# CPU.net
KiCad netlist of a schematic drawn in Altium Designer
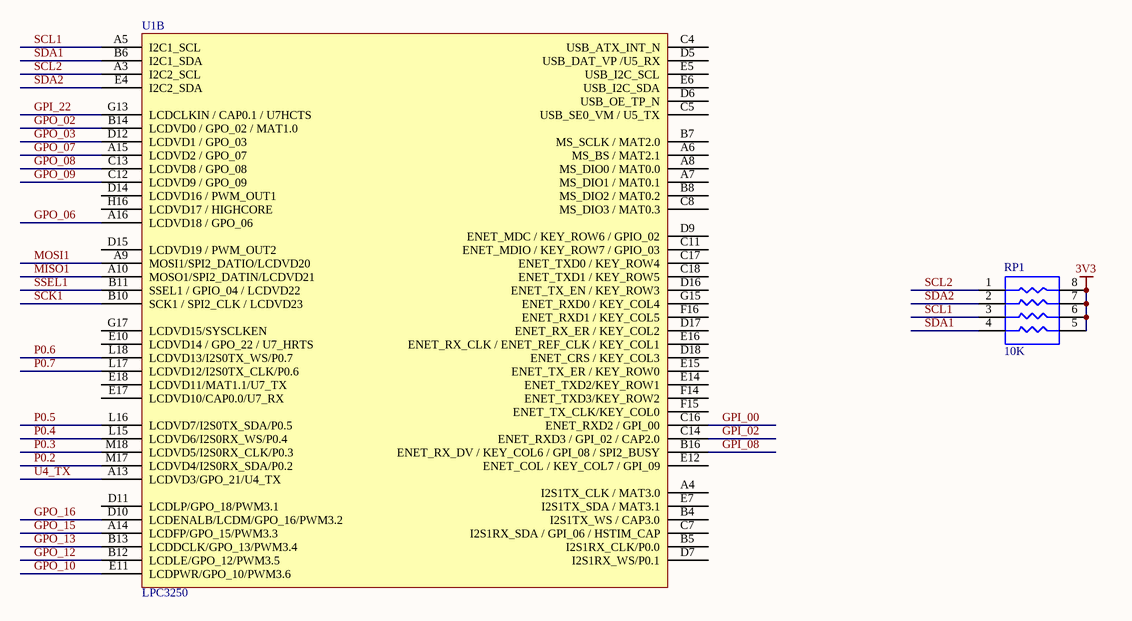
[diagram p0: CPU.SchDoc]

(export (version "E")
  (design (tool "Eeschema 10.0.6"))
  (components
    (comp (ref "RP1") (value "10K") (footprint "PZ-4-0.8B") (libsource (lib "MyProject1") (part "RP")))
    (comp (ref "U1") (value "LPC3250") (footprint "TFBGA296") (libsource (lib "MyProject1") (part "LPC3250")))
  )
  (nets
    (net (code "1") (name "/GPI_00") (class "Default")
      (node (ref "U1") (pin "C16") (pinfunction "ENET_RXD2_/_GPI_00_C16") (pintype "passive"))
    )
    (net (code "2") (name "/GPI_02") (class "Default")
      (node (ref "U1") (pin "C14") (pinfunction "ENET_RXD3_/_GPI_02_/_CAP2.0_C14") (pintype "passive"))
    )
    (net (code "3") (name "/GPI_08") (class "Default")
      (node (ref "U1") (pin "B16") (pinfunction "ENET_RX_DV_/_KEY_COL6_/_GPI_08_/_SPI2_BUSY_B16") (pintype "passive"))
    )
    (net (code "4") (name "/GPI_22") (class "Default")
      (node (ref "U1") (pin "G13") (pinfunction "LCDCLKIN_/_CAP0.1_/_U7HCTS_G13") (pintype "passive"))
    )
    (net (code "5") (name "/GPO_02") (class "Default")
      (node (ref "U1") (pin "B14") (pinfunction "LCDVD0_/_GPO_02_/_MAT1.0_B14") (pintype "passive"))
    )
    (net (code "6") (name "/GPO_03") (class "Default")
      (node (ref "U1") (pin "D12") (pinfunction "LCDVD1_/_GPO_03_D12") (pintype "passive"))
    )
    (net (code "7") (name "/GPO_06") (class "Default")
      (node (ref "U1") (pin "A16") (pinfunction "LCDVD18_/_GPO_06_A16") (pintype "passive"))
    )
    (net (code "8") (name "/GPO_07") (class "Default")
      (node (ref "U1") (pin "A15") (pinfunction "LCDVD2_/_GPO_07_A15") (pintype "passive"))
    )
    (net (code "9") (name "/GPO_08") (class "Default")
      (node (ref "U1") (pin "C13") (pinfunction "LCDVD8_/_GPO_08_C13") (pintype "passive"))
    )
    (net (code "10") (name "/GPO_09") (class "Default")
      (node (ref "U1") (pin "C12") (pinfunction "LCDVD9_/_GPO_09_C12") (pintype "passive"))
    )
    (net (code "11") (name "/GPO_10") (class "Default")
      (node (ref "U1") (pin "E11") (pinfunction "LCDPWR/GPO_10/PWM3.6_E11") (pintype "passive"))
    )
    (net (code "12") (name "/GPO_12") (class "Default")
      (node (ref "U1") (pin "B12") (pinfunction "LCDLE/GPO_12/PWM3.5_B12") (pintype "passive"))
    )
    (net (code "13") (name "/GPO_13") (class "Default")
      (node (ref "U1") (pin "B13") (pinfunction "LCDDCLK/GPO_13/PWM3.4_B13") (pintype "passive"))
    )
    (net (code "14") (name "/GPO_15") (class "Default")
      (node (ref "U1") (pin "A14") (pinfunction "LCDFP/GPO_15/PWM3.3_A14") (pintype "passive"))
    )
    (net (code "15") (name "/GPO_16") (class "Default")
      (node (ref "U1") (pin "D10") (pinfunction "LCDENALB/LCDM/GPO_16/PWM3.2_D10") (pintype "passive"))
    )
    (net (code "16") (name "/MISO1") (class "Default")
      (node (ref "U1") (pin "A10") (pinfunction "MOSO1/SPI2_DATIN/LCDVD21_A10") (pintype "passive"))
    )
    (net (code "17") (name "/MOSI1") (class "Default")
      (node (ref "U1") (pin "A9") (pinfunction "MOSI1/SPI2_DATIO/LCDVD20_A9") (pintype "passive"))
    )
    (net (code "18") (name "/P0.2") (class "Default")
      (node (ref "U1") (pin "M17") (pinfunction "LCDVD4/I2S0RX_SDA/P0.2_M17") (pintype "passive"))
    )
    (net (code "19") (name "/P0.3") (class "Default")
      (node (ref "U1") (pin "M18") (pinfunction "LCDVD5/I2S0RX_CLK/P0.3_M18") (pintype "passive"))
    )
    (net (code "20") (name "/P0.4") (class "Default")
      (node (ref "U1") (pin "L15") (pinfunction "LCDVD6/I2S0RX_WS/P0.4_L15") (pintype "passive"))
    )
    (net (code "21") (name "/P0.5") (class "Default")
      (node (ref "U1") (pin "L16") (pinfunction "LCDVD7/I2S0TX_SDA/P0.5_L16") (pintype "passive"))
    )
    (net (code "22") (name "/P0.6") (class "Default")
      (node (ref "U1") (pin "L18") (pinfunction "LCDVD13/I2S0TX_WS/P0.7_L18") (pintype "passive"))
    )
    (net (code "23") (name "/P0.7") (class "Default")
      (node (ref "U1") (pin "L17") (pinfunction "LCDVD12/I2S0TX_CLK/P0.6_L17") (pintype "passive"))
    )
    (net (code "24") (name "/SCK1") (class "Default")
      (node (ref "U1") (pin "B10") (pinfunction "SCK1_/_SPI2_CLK_/_LCDVD23_B10") (pintype "passive"))
    )
    (net (code "25") (name "/SCL1") (class "Default")
      (node (ref "RP1") (pin "3") (pinfunction "3_3") (pintype "passive"))
      (node (ref "U1") (pin "A5") (pinfunction "I2C1_SCL_A5") (pintype "passive"))
    )
    (net (code "26") (name "/SCL2") (class "Default")
      (node (ref "RP1") (pin "1") (pinfunction "1_1") (pintype "passive"))
      (node (ref "U1") (pin "A3") (pinfunction "I2C2_SCL_A3") (pintype "passive"))
    )
    (net (code "27") (name "/SDA1") (class "Default")
      (node (ref "RP1") (pin "4") (pinfunction "4_4") (pintype "passive"))
      (node (ref "U1") (pin "B6") (pinfunction "I2C1_SDA_B6") (pintype "passive"))
    )
    (net (code "28") (name "/SDA2") (class "Default")
      (node (ref "RP1") (pin "2") (pinfunction "2_2") (pintype "passive"))
      (node (ref "U1") (pin "E4") (pinfunction "I2C2_SDA_E4") (pintype "passive"))
    )
    (net (code "29") (name "/SSEL1") (class "Default")
      (node (ref "U1") (pin "B11") (pinfunction "SSEL1_/_GPIO_04_/_LCDVD22_B11") (pintype "passive"))
    )
    (net (code "30") (name "/U4_TX") (class "Default")
      (node (ref "U1") (pin "A13") (pinfunction "LCDVD3/GPO_21/U4_TX_A13") (pintype "passive"))
    )
    (net (code "31") (name "3V3") (class "Default")
      (node (ref "RP1") (pin "5") (pinfunction "5_5") (pintype "passive"))
      (node (ref "RP1") (pin "6") (pinfunction "6_6") (pintype "passive"))
      (node (ref "RP1") (pin "7") (pinfunction "7_7") (pintype "passive"))
      (node (ref "RP1") (pin "8") (pinfunction "8_8") (pintype "passive"))
    )
    (net (code "32") (name "unconnected-(U1B-ENET_COL_{slash}_KEY_COL7_{slash}_GPI_09-PadE12)") (class "Default")
      (node (ref "U1") (pin "E12") (pinfunction "ENET_COL_/_KEY_COL7_/_GPI_09_E12") (pintype "passive"))
    )
    (net (code "33") (name "unconnected-(U1B-ENET_CRS_{slash}_KEY_COL3-PadD18)") (class "Default")
      (node (ref "U1") (pin "D18") (pinfunction "ENET_CRS_/_KEY_COL3_D18") (pintype "passive"))
    )
    (net (code "34") (name "unconnected-(U1B-ENET_MDC_{slash}_KEY_ROW6_{slash}_GPIO_02-PadD9)") (class "Default")
      (node (ref "U1") (pin "D9") (pinfunction "ENET_MDC_/_KEY_ROW6_/_GPIO_02_D9") (pintype "passive"))
    )
    (net (code "35") (name "unconnected-(U1B-ENET_MDIO_{slash}_KEY_ROW7_{slash}_GPIO_03-PadC11)") (class "Default")
      (node (ref "U1") (pin "C11") (pinfunction "ENET_MDIO_/_KEY_ROW7_/_GPIO_03_C11") (pintype "passive"))
    )
    (net (code "36") (name "unconnected-(U1B-ENET_RXD0_{slash}_KEY_COL4-PadG15)") (class "Default")
      (node (ref "U1") (pin "G15") (pinfunction "ENET_RXD0_/_KEY_COL4_G15") (pintype "passive"))
    )
    (net (code "37") (name "unconnected-(U1B-ENET_RXD1_{slash}_KEY_COL5-PadF16)") (class "Default")
      (node (ref "U1") (pin "F16") (pinfunction "ENET_RXD1_/_KEY_COL5_F16") (pintype "passive"))
    )
    (net (code "38") (name "unconnected-(U1B-ENET_RX_CLK_{slash}_ENET_REF_CLK_{slash}_KEY_COL1-PadE16)") (class "Default")
      (node (ref "U1") (pin "E16") (pinfunction "ENET_RX_CLK_/_ENET_REF_CLK_/_KEY_COL1_E16") (pintype "passive"))
    )
    (net (code "39") (name "unconnected-(U1B-ENET_RX_ER_{slash}_KEY_COL2-PadD17)") (class "Default")
      (node (ref "U1") (pin "D17") (pinfunction "ENET_RX_ER_/_KEY_COL2_D17") (pintype "passive"))
    )
    (net (code "40") (name "unconnected-(U1B-ENET_TXD0_{slash}_KEY_ROW4-PadC17)") (class "Default")
      (node (ref "U1") (pin "C17") (pinfunction "ENET_TXD0_/_KEY_ROW4_C17") (pintype "passive"))
    )
    (net (code "41") (name "unconnected-(U1B-ENET_TXD1_{slash}_KEY_ROW5-PadC18)") (class "Default")
      (node (ref "U1") (pin "C18") (pinfunction "ENET_TXD1_/_KEY_ROW5_C18") (pintype "passive"))
    )
    (net (code "42") (name "unconnected-(U1B-ENET_TXD2{slash}KEY_ROW1-PadE14)") (class "Default")
      (node (ref "U1") (pin "E14") (pinfunction "ENET_TXD2/KEY_ROW1_E14") (pintype "passive"))
    )
    (net (code "43") (name "unconnected-(U1B-ENET_TXD3{slash}KEY_ROW2-PadF14)") (class "Default")
      (node (ref "U1") (pin "F14") (pinfunction "ENET_TXD3/KEY_ROW2_F14") (pintype "passive"))
    )
    (net (code "44") (name "unconnected-(U1B-ENET_TX_CLK{slash}KEY_COL0-PadF15)") (class "Default")
      (node (ref "U1") (pin "F15") (pinfunction "ENET_TX_CLK/KEY_COL0_F15") (pintype "passive"))
    )
    (net (code "45") (name "unconnected-(U1B-ENET_TX_EN_{slash}_KEY_ROW3-PadD16)") (class "Default")
      (node (ref "U1") (pin "D16") (pinfunction "ENET_TX_EN_/_KEY_ROW3_D16") (pintype "passive"))
    )
    (net (code "46") (name "unconnected-(U1B-ENET_TX_ER_{slash}_KEY_ROW0-PadE15)") (class "Default")
      (node (ref "U1") (pin "E15") (pinfunction "ENET_TX_ER_/_KEY_ROW0_E15") (pintype "passive"))
    )
    (net (code "47") (name "unconnected-(U1B-I2S1RX_CLK{slash}P0.0-PadB5)") (class "Default")
      (node (ref "U1") (pin "B5") (pinfunction "I2S1RX_CLK/P0.0_B5") (pintype "passive"))
    )
    (net (code "48") (name "unconnected-(U1B-I2S1RX_SDA_{slash}_GPI_06_{slash}_HSTIM_CAP-PadC7)") (class "Default")
      (node (ref "U1") (pin "C7") (pinfunction "I2S1RX_SDA_/_GPI_06_/_HSTIM_CAP_C7") (pintype "passive"))
    )
    (net (code "49") (name "unconnected-(U1B-I2S1RX_WS{slash}P0.1-PadD7)") (class "Default")
      (node (ref "U1") (pin "D7") (pinfunction "I2S1RX_WS/P0.1_D7") (pintype "passive"))
    )
    (net (code "50") (name "unconnected-(U1B-I2S1TX_CLK_{slash}_MAT3.0-PadA4)") (class "Default")
      (node (ref "U1") (pin "A4") (pinfunction "I2S1TX_CLK_/_MAT3.0_A4") (pintype "passive"))
    )
    (net (code "51") (name "unconnected-(U1B-I2S1TX_SDA_{slash}_MAT3.1-PadE7)") (class "Default")
      (node (ref "U1") (pin "E7") (pinfunction "I2S1TX_SDA_/_MAT3.1_E7") (pintype "passive"))
    )
    (net (code "52") (name "unconnected-(U1B-I2S1TX_WS_{slash}_CAP3.0-PadB4)") (class "Default")
      (node (ref "U1") (pin "B4") (pinfunction "I2S1TX_WS_/_CAP3.0_B4") (pintype "passive"))
    )
    (net (code "53") (name "unconnected-(U1B-LCDLP{slash}GPO_18{slash}PWM3.1-PadD11)") (class "Default")
      (node (ref "U1") (pin "D11") (pinfunction "LCDLP/GPO_18/PWM3.1_D11") (pintype "passive"))
    )
    (net (code "54") (name "unconnected-(U1B-LCDVD10{slash}CAP0.0{slash}U7_RX-PadE17)") (class "Default")
      (node (ref "U1") (pin "E17") (pinfunction "LCDVD10/CAP0.0/U7_RX_E17") (pintype "passive"))
    )
    (net (code "55") (name "unconnected-(U1B-LCDVD11{slash}MAT1.1{slash}U7_TX-PadE18)") (class "Default")
      (node (ref "U1") (pin "E18") (pinfunction "LCDVD11/MAT1.1/U7_TX_E18") (pintype "passive"))
    )
    (net (code "56") (name "unconnected-(U1B-LCDVD14_{slash}_GPO_22_{slash}_U7_HRTS-PadE10)") (class "Default")
      (node (ref "U1") (pin "E10") (pinfunction "LCDVD14_/_GPO_22_/_U7_HRTS_E10") (pintype "passive"))
    )
    (net (code "57") (name "unconnected-(U1B-LCDVD15{slash}SYSCLKEN-PadG17)") (class "Default")
      (node (ref "U1") (pin "G17") (pinfunction "LCDVD15/SYSCLKEN_G17") (pintype "passive"))
    )
    (net (code "58") (name "unconnected-(U1B-LCDVD16_{slash}_PWM_OUT1-PadD14)") (class "Default")
      (node (ref "U1") (pin "D14") (pinfunction "LCDVD16_/_PWM_OUT1_D14") (pintype "passive"))
    )
    (net (code "59") (name "unconnected-(U1B-LCDVD17_{slash}_HIGHCORE-PadH16)") (class "Default")
      (node (ref "U1") (pin "H16") (pinfunction "LCDVD17_/_HIGHCORE_H16") (pintype "passive"))
    )
    (net (code "60") (name "unconnected-(U1B-LCDVD19_{slash}_PWM_OUT2-PadD15)") (class "Default")
      (node (ref "U1") (pin "D15") (pinfunction "LCDVD19_/_PWM_OUT2_D15") (pintype "passive"))
    )
    (net (code "61") (name "unconnected-(U1B-MS_BS_{slash}_MAT2.1-PadA6)") (class "Default")
      (node (ref "U1") (pin "A6") (pinfunction "MS_BS_/_MAT2.1_A6") (pintype "passive"))
    )
    (net (code "62") (name "unconnected-(U1B-MS_DIO0_{slash}_MAT0.0-PadA8)") (class "Default")
      (node (ref "U1") (pin "A8") (pinfunction "MS_DIO0_/_MAT0.0_A8") (pintype "passive"))
    )
    (net (code "63") (name "unconnected-(U1B-MS_DIO1_{slash}_MAT0.1-PadA7)") (class "Default")
      (node (ref "U1") (pin "A7") (pinfunction "MS_DIO1_/_MAT0.1_A7") (pintype "passive"))
    )
    (net (code "64") (name "unconnected-(U1B-MS_DIO2_{slash}_MAT0.2-PadB8)") (class "Default")
      (node (ref "U1") (pin "B8") (pinfunction "MS_DIO2_/_MAT0.2_B8") (pintype "passive"))
    )
    (net (code "65") (name "unconnected-(U1B-MS_DIO3_{slash}_MAT0.3-PadC8)") (class "Default")
      (node (ref "U1") (pin "C8") (pinfunction "MS_DIO3_/_MAT0.3_C8") (pintype "passive"))
    )
    (net (code "66") (name "unconnected-(U1B-MS_SCLK_{slash}_MAT2.0-PadB7)") (class "Default")
      (node (ref "U1") (pin "B7") (pinfunction "MS_SCLK_/_MAT2.0_B7") (pintype "passive"))
    )
    (net (code "67") (name "unconnected-(U1B-USB_ATX_INT_N-PadC4)") (class "Default")
      (node (ref "U1") (pin "C4") (pinfunction "USB_ATX_INT_N_C4") (pintype "passive"))
    )
    (net (code "68") (name "unconnected-(U1B-USB_DAT_VP_{slash}U5_RX-PadD5)") (class "Default")
      (node (ref "U1") (pin "D5") (pinfunction "USB_DAT_VP_/U5_RX_D5") (pintype "passive"))
    )
    (net (code "69") (name "unconnected-(U1B-USB_I2C_SCL-PadE5)") (class "Default")
      (node (ref "U1") (pin "E5") (pinfunction "USB_I2C_SCL_E5") (pintype "passive"))
    )
    (net (code "70") (name "unconnected-(U1B-USB_I2C_SDA-PadE6)") (class "Default")
      (node (ref "U1") (pin "E6") (pinfunction "USB_I2C_SDA_E6") (pintype "passive"))
    )
    (net (code "71") (name "unconnected-(U1B-USB_OE_TP_N-PadD6)") (class "Default")
      (node (ref "U1") (pin "D6") (pinfunction "USB_OE_TP_N_D6") (pintype "passive"))
    )
    (net (code "72") (name "unconnected-(U1B-USB_SE0_VM_{slash}_U5_TX-PadC5)") (class "Default")
      (node (ref "U1") (pin "C5") (pinfunction "USB_SE0_VM_/_U5_TX_C5") (pintype "passive"))
    )
  )
)
